# uMultimeter_ExpProbeA_Sch.net
KiCad netlist of a schematic drawn in Altium Designer
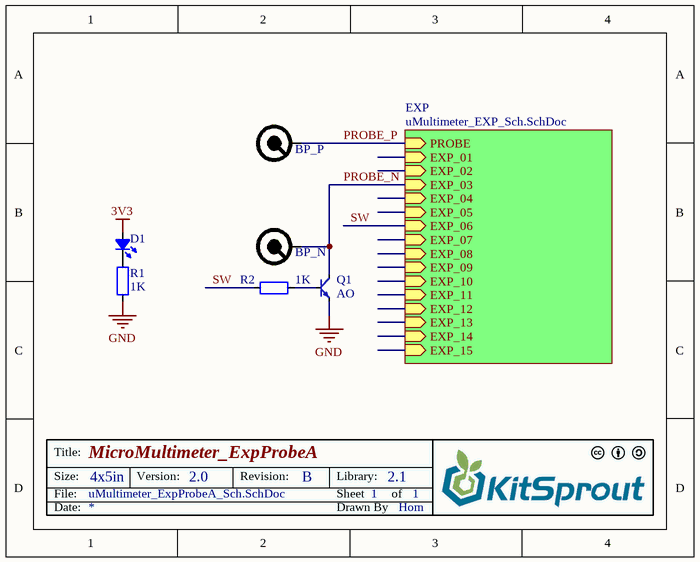
[diagram p0: uMultimeter_ExpProbeA_Sch.SchDoc]

(export (version "E")
  (design (tool "Eeschema 10.0.6"))
  (components
    (comp (ref "BP_N")
      (value "BananaPlugs")
      (footprint "PCB_ConnectorCable:BananaPlugs_Black")
      (libsource (lib "SCH_Connector") (part "BananaPlugs"))
    )
    (comp (ref "BP_P")
      (value "BananaPlugs")
      (footprint "PCB_ConnectorCable:BananaPlugs_Red")
      (libsource (lib "SCH_Connector") (part "BananaPlugs"))
    )
    (comp (ref "D1")
      (value "LED_0805")
      (footprint "PCB_ActiveLED:LED_0805_BLUE")
      (description "LED")
      (libsource (lib "SCH_Active") (part "LED_0805"))
    )
    (comp (ref "Q1")
      (value "AO")
      (footprint "PCB_IntegratedCircuit:SOT23-3")
      (description "Transistor")
      (fields (field (name "Comment") "BJT_NPN"))
      (libsource (lib "SCH_Active") (part "BJT_NPN"))
    )
    (comp (ref "R1")
      (value "1K")
      (footprint "PCB_PassiveRes:RES_0603")
      (description "Resistor")
      (fields (field (name "Comment") "Res_0603"))
      (libsource (lib "SCH_Passive") (part "Res_0603"))
    )
    (comp (ref "R2")
      (value "1K")
      (footprint "PCB_PassiveRes:RES_0603")
      (description "Resistor")
      (fields (field (name "Comment") "Res_0603"))
      (libsource (lib "") (part "Res_0603_1"))
    )
  )
  (nets
    (net (code "14") (name "/PROBE_N") (class "Default")
      (node (ref "BP_N") (pin "1") (pinfunction "1_1") (pintype "passive"))
      (node (ref "Q1") (pin "3") (pinfunction "C_3") (pintype "passive"))
    )
    (net (code "15") (name "/PROBE_P") (class "Default")
      (node (ref "BP_P") (pin "1") (pinfunction "1_1") (pintype "passive"))
    )
    (net (code "16") (name "/SW") (class "Default")
      (node (ref "R2") (pin "1") (pinfunction "1_1") (pintype "passive"))
    )
    (net (code "17") (name "3V3") (class "Default")
      (node (ref "D1") (pin "1") (pinfunction "A_1") (pintype "passive"))
    )
    (net (code "18") (name "GND") (class "Default")
      (node (ref "Q1") (pin "2") (pinfunction "E_2") (pintype "passive"))
      (node (ref "R1") (pin "2") (pinfunction "2_2") (pintype "passive"))
    )
    (net (code "19") (name "Net-(D1-K)") (class "Default")
      (node (ref "D1") (pin "2") (pinfunction "K_2") (pintype "passive"))
      (node (ref "R1") (pin "1") (pinfunction "1_1") (pintype "passive"))
    )
    (net (code "20") (name "Net-(Q1-B)") (class "Default")
      (node (ref "Q1") (pin "1") (pinfunction "B_1") (pintype "passive"))
      (node (ref "R2") (pin "2") (pinfunction "2_2") (pintype "passive"))
    )
  )
)
